# tusb3410.net
KiCad netlist of a schematic drawn in Altium Designer
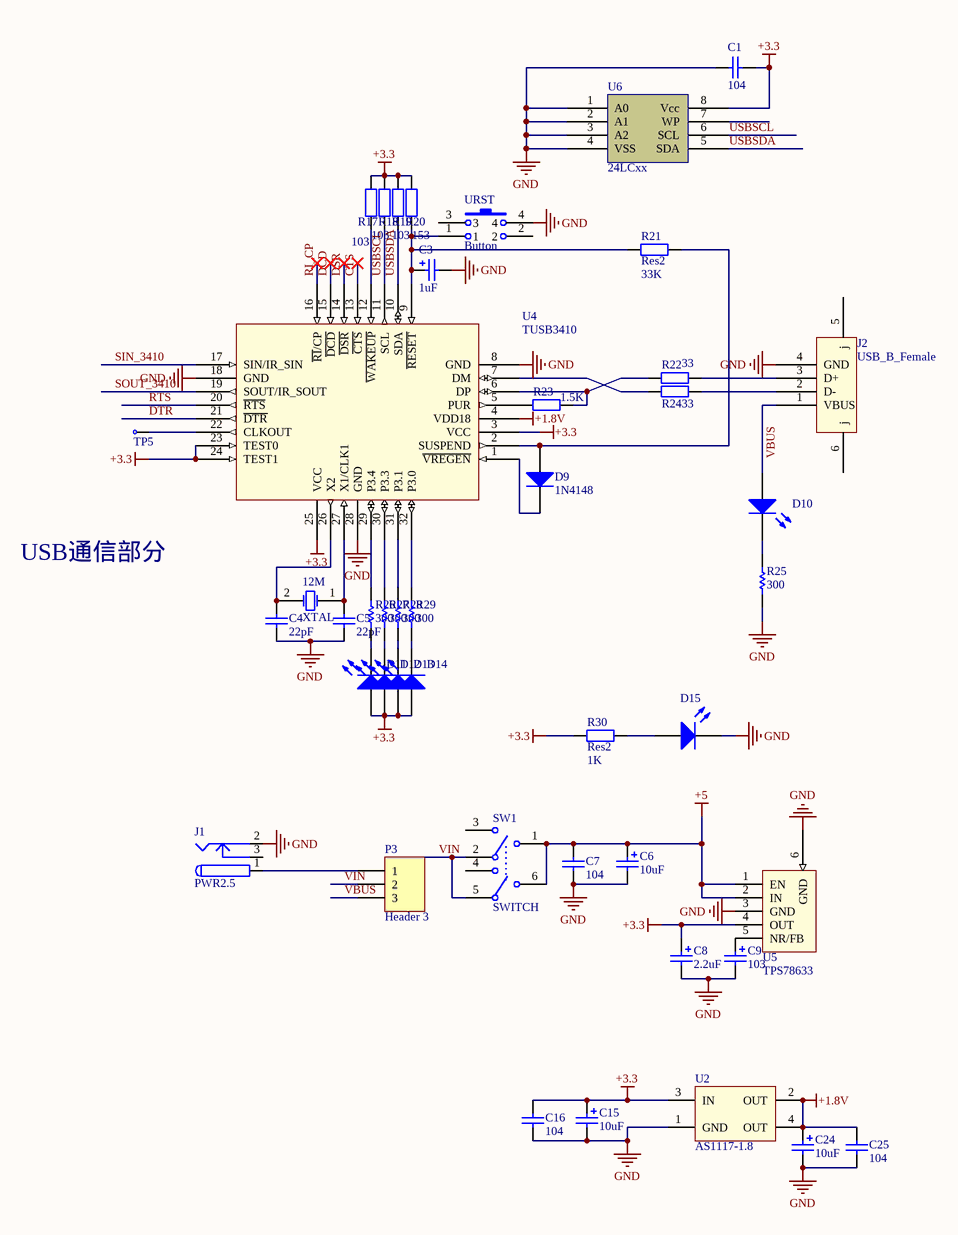
[diagram p0: tusb3410.SchDoc]

(export (version "E")
  (design (tool "Eeschema 10.0.6"))
  (components
    (comp (ref "12M")
      (value "XTAL")
      (footprint "GJA-M")
      (description "Crystal Oscillator")
      (fields (field (name "PUBLISHER") "Altium Limited"))
      (libsource (lib "WENSHI") (part "XTAL"))
    )
    (comp (ref "C1")
      (value "104")
      (footprint "C0805")
      (description "Capacitor")
      (fields (field (name "Comment") "Cap") (field (name "PUBLISHER") "Altium Limited"))
      (libsource (lib "WENSHI") (part "Cap"))
    )
    (comp (ref "C3")
      (value "1uF")
      (footprint "C5.3")
      (description "Polarized Capacitor (Radial)")
      (fields (field (name "Comment") "Cap Pol1") (field (name "PUBLISHER") "Altium Limited"))
      (libsource (lib "WENSHI") (part "Cap Pol1"))
    )
    (comp (ref "C4")
      (value "22pF")
      (footprint "C0805")
      (description "Capacitor")
      (fields (field (name "Comment") "Cap") (field (name "PUBLISHER") "Altium Limited"))
      (libsource (lib "Miscellaneous Devices") (part "Cap"))
    )
    (comp (ref "C5")
      (value "22pF")
      (footprint "C0805")
      (description "Capacitor")
      (fields (field (name "Comment") "Cap") (field (name "PUBLISHER") "Altium Limited"))
      (libsource (lib "Miscellaneous Devices") (part "Cap"))
    )
    (comp (ref "C6")
      (value "10uF")
      (footprint "C5.3")
      (description "Polarized Capacitor (Radial)")
      (fields (field (name "Comment") "Cap Pol1") (field (name "PUBLISHER") "Altium Limited"))
      (libsource (lib "WENSHI") (part "Cap Pol1"))
    )
    (comp (ref "C7")
      (value "104")
      (footprint "C0805")
      (description "Capacitor")
      (fields (field (name "Comment") "Cap") (field (name "PUBLISHER") "Altium Limited"))
      (libsource (lib "WENSHI") (part "Cap"))
    )
    (comp (ref "C8")
      (value "2.2uF")
      (footprint "C5.3")
      (description "Polarized Capacitor (Radial)")
      (fields (field (name "Comment") "Cap Pol1") (field (name "PUBLISHER") "Altium Limited"))
      (libsource (lib "WENSHI") (part "Cap Pol1"))
    )
    (comp (ref "C9")
      (value "103")
      (footprint "C5.3")
      (description "Polarized Capacitor (Radial)")
      (fields (field (name "Comment") "Cap Pol1") (field (name "PUBLISHER") "Altium Limited"))
      (libsource (lib "WENSHI") (part "Cap Pol1"))
    )
    (comp (ref "C15")
      (value "10uF")
      (footprint "C5.3")
      (description "Polarized Capacitor (Radial)")
      (fields (field (name "Comment") "Cap Pol1") (field (name "PUBLISHER") "Altium Limited"))
      (libsource (lib "WENSHI") (part "Cap Pol1"))
    )
    (comp (ref "C16")
      (value "104")
      (footprint "C0805")
      (description "Capacitor")
      (fields (field (name "Comment") "Cap") (field (name "PUBLISHER") "Altium Limited"))
      (libsource (lib "WENSHI") (part "Cap"))
    )
    (comp (ref "C24")
      (value "10uF")
      (footprint "C5.3")
      (description "Polarized Capacitor (Radial)")
      (fields (field (name "Comment") "Cap Pol1") (field (name "PUBLISHER") "Altium Limited"))
      (libsource (lib "WENSHI") (part "Cap Pol1"))
    )
    (comp (ref "C25")
      (value "104")
      (footprint "C0805")
      (description "Capacitor")
      (fields (field (name "Comment") "Cap") (field (name "PUBLISHER") "Altium Limited"))
      (libsource (lib "WENSHI") (part "Cap"))
    )
    (comp (ref "D9")
      (value "1N4148")
      (footprint "DO-35")
      (description "High Conductance Fast Diode")
      (fields (field (name "PUBLISHER") "Altium Limited"))
      (libsource (lib "Miscellaneous Devices") (part "Diode 1N4148"))
    )
    (comp (ref "D10")
      (value "LED1")
      (footprint "LED")
      (description "Typical RED GaAs LED")
      (fields (field (name "PUBLISHER") "Altium Limited"))
      (libsource (lib "WENSHI") (part "LED1"))
    )
    (comp (ref "D11")
      (value "LED1")
      (footprint "C0805")
      (description "Typical RED GaAs LED")
      (fields (field (name "PUBLISHER") "Altium Limited"))
      (libsource (lib "WENSHI") (part "LED1"))
    )
    (comp (ref "D12")
      (value "LED1")
      (footprint "C0805")
      (description "Typical RED GaAs LED")
      (fields (field (name "PUBLISHER") "Altium Limited"))
      (libsource (lib "WENSHI") (part "LED1"))
    )
    (comp (ref "D13")
      (value "LED1")
      (footprint "C0805")
      (description "Typical RED GaAs LED")
      (fields (field (name "PUBLISHER") "Altium Limited"))
      (libsource (lib "WENSHI") (part "LED1"))
    )
    (comp (ref "D14")
      (value "LED1")
      (footprint "C0805")
      (description "Typical RED GaAs LED")
      (fields (field (name "PUBLISHER") "Altium Limited"))
      (libsource (lib "WENSHI") (part "LED1"))
    )
    (comp (ref "D15")
      (value "LED1")
      (footprint "LED")
      (description "Typical RED GaAs LED")
      (fields (field (name "PUBLISHER") "Altium Limited"))
      (libsource (lib "WENSHI") (part "LED1"))
    )
    (comp (ref "J1")
      (value "PWR2.5")
      (footprint "DCJACK")
      (description "Low Voltage Power Supply Connector")
      (fields (field (name "PUBLISHER") "Altium Limited"))
      (libsource (lib "WENSHI") (part "PWR2.5"))
    )
    (comp (ref "J2")
      (value "USB_B_Female")
      (footprint "USB_B_Female")
      (libsource (lib "WENSHI") (part "USB_B_Female"))
    )
    (comp (ref "P3")
      (value "Header 3")
      (footprint "HDR1X3")
      (description "Header, 3-Pin")
      (fields (field (name "PUBLISHER") "Altium Limited"))
      (libsource (lib "Miscellaneous Connectors") (part "Header 3"))
    )
    (comp (ref "R17")
      (value "103")
      (footprint "c0805")
      (description "Resistor")
      (fields (field (name "Comment") "Res2") (field (name "PUBLISHER") "Altium Limited"))
      (libsource (lib "WENSHI") (part "Res2"))
    )
    (comp (ref "R18")
      (value "103")
      (footprint "c0805")
      (description "Resistor")
      (fields (field (name "Comment") "Res2") (field (name "PUBLISHER") "Altium Limited"))
      (libsource (lib "WENSHI") (part "Res2"))
    )
    (comp (ref "R19")
      (value "103")
      (footprint "c0805")
      (description "Resistor")
      (fields (field (name "Comment") "Res2") (field (name "PUBLISHER") "Altium Limited"))
      (libsource (lib "WENSHI") (part "Res2"))
    )
    (comp (ref "R20")
      (value "153")
      (footprint "c0805")
      (description "Resistor")
      (fields (field (name "Comment") "Res2") (field (name "PUBLISHER") "Altium Limited"))
      (libsource (lib "WENSHI") (part "Res2"))
    )
    (comp (ref "R21")
      (value "Res2")
      (footprint "c0805")
      (description "Resistor")
      (fields (field (name "ALTIUM_VALUE") "33K") (field (name "PUBLISHER") "Altium Limited"))
      (libsource (lib "") (part "Res2_1"))
    )
    (comp (ref "R22")
      (value "33")
      (footprint "c0805")
      (description "Resistor")
      (fields (field (name "Comment") "Res2") (field (name "PUBLISHER") "Altium Limited"))
      (libsource (lib "") (part "Res2_1"))
    )
    (comp (ref "R23")
      (value "1.5K")
      (footprint "c0805")
      (description "Resistor")
      (fields (field (name "Comment") "Res2") (field (name "PUBLISHER") "Altium Limited"))
      (libsource (lib "") (part "Res2_1"))
    )
    (comp (ref "R24")
      (value "33")
      (footprint "c0805")
      (description "Resistor")
      (fields (field (name "Comment") "Res2") (field (name "PUBLISHER") "Altium Limited"))
      (libsource (lib "") (part "Res2_1"))
    )
    (comp (ref "R25")
      (value "300")
      (footprint "C0805")
      (description "Resistor")
      (fields (field (name "Comment") "Res1") (field (name "PUBLISHER") "Altium Limited"))
      (libsource (lib "Miscellaneous Devices") (part "Res1"))
    )
    (comp (ref "R26")
      (value "300")
      (footprint "C0805")
      (description "Resistor")
      (fields (field (name "Comment") "Res1") (field (name "PUBLISHER") "Altium Limited"))
      (libsource (lib "Miscellaneous Devices") (part "Res1"))
    )
    (comp (ref "R27")
      (value "300")
      (footprint "C0805")
      (description "Resistor")
      (fields (field (name "Comment") "Res1") (field (name "PUBLISHER") "Altium Limited"))
      (libsource (lib "Miscellaneous Devices") (part "Res1"))
    )
    (comp (ref "R28")
      (value "300")
      (footprint "C0805")
      (description "Resistor")
      (fields (field (name "Comment") "Res1") (field (name "PUBLISHER") "Altium Limited"))
      (libsource (lib "Miscellaneous Devices") (part "Res1"))
    )
    (comp (ref "R29")
      (value "300")
      (footprint "C0805")
      (description "Resistor")
      (fields (field (name "Comment") "Res1") (field (name "PUBLISHER") "Altium Limited"))
      (libsource (lib "Miscellaneous Devices") (part "Res1"))
    )
    (comp (ref "R30")
      (value "Res2")
      (footprint "c0805")
      (description "Resistor")
      (fields (field (name "ALTIUM_VALUE") "1K") (field (name "PUBLISHER") "Altium Limited"))
      (libsource (lib "") (part "Res2_1"))
    )
    (comp (ref "SW1") (value "SWITCH") (footprint "DPDT-6") (libsource (lib "WENSHI") (part "SW-DPDT")))
    (comp (ref "TP5")
      (value "TestPoint")
      (footprint "TESTPOINT")
      (description "TespPoint")
      (libsource (lib "2812") (part "TestPoint"))
    )
    (comp (ref "U2")
      (value "AS1117-1.8")
      (footprint "SOT-223")
      (libsource (lib "WENSHI") (part "AS1117-3.3"))
    )
    (comp (ref "U4")
      (value "TUSB3410")
      (footprint "DMC68HC908JL8")
      (libsource (lib "TUSB3410") (part "TUSB3410"))
    )
    (comp (ref "U5")
      (value "TPS78633")
      (footprint "PSFM_G5")
      (description "3.3V Power")
      (libsource (lib "WENSHI") (part "TPS78633"))
    )
    (comp (ref "U6") (value "24LCxx") (footprint "DIP-8") (libsource (lib "2812") (part "24LCxx")))
    (comp (ref "URST") (value "Button") (footprint "SW-6") (libsource (lib "WENSHI") (part "Button_4")))
  )
  (nets
    (net (code "1") (name "+1.8V") (class "Default")
      (node (ref "C24") (pin "1") (pinfunction "1_1") (pintype "passive"))
      (node (ref "C25") (pin "2") (pinfunction "2_2") (pintype "passive"))
      (node (ref "U2") (pin "2") (pinfunction "OUT_2") (pintype "passive"))
      (node (ref "U2") (pin "4") (pinfunction "OUT_4") (pintype "passive"))
      (node (ref "U4") (pin "4") (pinfunction "VDD18_4") (pintype "power_in"))
    )
    (net (code "2") (name "+3.3") (class "Default")
      (node (ref "C1") (pin "2") (pinfunction "2_2") (pintype "passive"))
      (node (ref "C15") (pin "1") (pinfunction "1_1") (pintype "passive"))
      (node (ref "C16") (pin "2") (pinfunction "2_2") (pintype "passive"))
      (node (ref "C8") (pin "1") (pinfunction "1_1") (pintype "passive"))
      (node (ref "D11") (pin "1") (pinfunction "A_1") (pintype "passive"))
      (node (ref "D12") (pin "1") (pinfunction "A_1") (pintype "passive"))
      (node (ref "D13") (pin "1") (pinfunction "A_1") (pintype "passive"))
      (node (ref "D14") (pin "1") (pinfunction "A_1") (pintype "passive"))
      (node (ref "R17") (pin "2") (pinfunction "2_2") (pintype "passive"))
      (node (ref "R18") (pin "2") (pinfunction "2_2") (pintype "passive"))
      (node (ref "R19") (pin "2") (pinfunction "2_2") (pintype "passive"))
      (node (ref "R20") (pin "2") (pinfunction "2_2") (pintype "passive"))
      (node (ref "R30") (pin "1") (pinfunction "1_1") (pintype "passive"))
      (node (ref "U2") (pin "3") (pinfunction "IN_3") (pintype "passive"))
      (node (ref "U4") (pin "23") (pinfunction "TEST0_23") (pintype "input"))
      (node (ref "U4") (pin "24") (pinfunction "TEST1_24") (pintype "input"))
      (node (ref "U4") (pin "25") (pinfunction "VCC_25") (pintype "power_in"))
      (node (ref "U4") (pin "3") (pinfunction "VCC_3") (pintype "power_in"))
      (node (ref "U5") (pin "4") (pinfunction "OUT_4") (pintype "passive"))
      (node (ref "U6") (pin "8") (pinfunction "Vcc_8") (pintype "passive"))
    )
    (net (code "3") (name "+5") (class "Default")
      (node (ref "C6") (pin "1") (pinfunction "1_1") (pintype "passive"))
      (node (ref "C7") (pin "2") (pinfunction "2_2") (pintype "passive"))
      (node (ref "SW1") (pin "1") (pinfunction "1_1") (pintype "passive"))
      (node (ref "SW1") (pin "6") (pinfunction "6_6") (pintype "passive"))
      (node (ref "U5") (pin "1") (pinfunction "EN_1") (pintype "passive"))
      (node (ref "U5") (pin "2") (pinfunction "IN_2") (pintype "passive"))
    )
    (net (code "4") (name "/CTS") (class "Default")
      (node (ref "U4") (pin "13") (pinfunction "~{CTS}_13") (pintype "input+no_connect"))
    )
    (net (code "5") (name "/DCD") (class "Default")
      (node (ref "U4") (pin "15") (pinfunction "~{DCD}_15") (pintype "input+no_connect"))
    )
    (net (code "6") (name "/DSR") (class "Default")
      (node (ref "U4") (pin "14") (pinfunction "~{DSR}_14") (pintype "input+no_connect"))
    )
    (net (code "7") (name "/DTR") (class "Default")
      (node (ref "U4") (pin "21") (pinfunction "~{DTR}_21") (pintype "output"))
    )
    (net (code "8") (name "/RI_CP") (class "Default")
      (node (ref "U4") (pin "16") (pinfunction "~{RI}/CP_16") (pintype "input+no_connect"))
    )
    (net (code "9") (name "/RTS") (class "Default")
      (node (ref "U4") (pin "20") (pinfunction "~{RTS}_20") (pintype "output"))
    )
    (net (code "10") (name "/SIN_3410") (class "Default")
      (node (ref "U4") (pin "17") (pinfunction "SIN/IR_SIN_17") (pintype "input"))
    )
    (net (code "11") (name "/SOUT_3410") (class "Default")
      (node (ref "U4") (pin "19") (pinfunction "SOUT/IR_SOUT_19") (pintype "output"))
    )
    (net (code "12") (name "/USBSCL") (class "Default")
      (node (ref "R18") (pin "1") (pinfunction "1_1") (pintype "passive"))
      (node (ref "U4") (pin "11") (pinfunction "SCL_11") (pintype "output"))
      (node (ref "U6") (pin "6") (pinfunction "SCL_6") (pintype "passive"))
    )
    (net (code "13") (name "/USBSDA") (class "Default")
      (node (ref "R19") (pin "1") (pinfunction "1_1") (pintype "passive"))
      (node (ref "U4") (pin "10") (pinfunction "SDA_10") (pintype "bidirectional"))
      (node (ref "U6") (pin "5") (pinfunction "SDA_5") (pintype "passive"))
    )
    (net (code "14") (name "/VBUS") (class "Default")
      (node (ref "D10") (pin "1") (pinfunction "A_1") (pintype "passive"))
      (node (ref "J2") (pin "1") (pinfunction "VBUS_1") (pintype "power_in"))
      (node (ref "P3") (pin "3") (pinfunction "3_3") (pintype "passive"))
    )
    (net (code "15") (name "/VIN") (class "Default")
      (node (ref "P3") (pin "2") (pinfunction "2_2") (pintype "passive"))
      (node (ref "SW1") (pin "2") (pinfunction "2_2") (pintype "passive"))
      (node (ref "SW1") (pin "5") (pinfunction "5_5") (pintype "passive"))
    )
    (net (code "16") (name "GND") (class "Default")
      (node (ref "C1") (pin "1") (pinfunction "1_1") (pintype "passive"))
      (node (ref "C15") (pin "2") (pinfunction "2_2") (pintype "passive"))
      (node (ref "C16") (pin "1") (pinfunction "1_1") (pintype "passive"))
      (node (ref "C24") (pin "2") (pinfunction "2_2") (pintype "passive"))
      (node (ref "C25") (pin "1") (pinfunction "1_1") (pintype "passive"))
      (node (ref "C3") (pin "2") (pinfunction "2_2") (pintype "passive"))
      (node (ref "C4") (pin "2") (pinfunction "2_2") (pintype "passive"))
      (node (ref "C5") (pin "2") (pinfunction "2_2") (pintype "passive"))
      (node (ref "C6") (pin "2") (pinfunction "2_2") (pintype "passive"))
      (node (ref "C7") (pin "1") (pinfunction "1_1") (pintype "passive"))
      (node (ref "C8") (pin "2") (pinfunction "2_2") (pintype "passive"))
      (node (ref "C9") (pin "2") (pinfunction "2_2") (pintype "passive"))
      (node (ref "D15") (pin "2") (pinfunction "K_2") (pintype "passive"))
      (node (ref "J1") (pin "2") (pinfunction "2_2") (pintype "power_in"))
      (node (ref "J2") (pin "4") (pinfunction "GND_4") (pintype "power_in"))
      (node (ref "R25") (pin "1") (pinfunction "1_1") (pintype "passive"))
      (node (ref "U2") (pin "1") (pinfunction "GND_1") (pintype "passive"))
      (node (ref "U4") (pin "18") (pinfunction "GND_18") (pintype "power_in"))
      (node (ref "U4") (pin "28") (pinfunction "GND_28") (pintype "power_in"))
      (node (ref "U4") (pin "8") (pinfunction "GND_8") (pintype "power_in"))
      (node (ref "U5") (pin "3") (pinfunction "GND_3") (pintype "passive"))
      (node (ref "U5") (pin "6") (pinfunction "GND_6") (pintype "input"))
      (node (ref "U6") (pin "1") (pinfunction "A0_1") (pintype "passive"))
      (node (ref "U6") (pin "2") (pinfunction "A1_2") (pintype "passive"))
      (node (ref "U6") (pin "3") (pinfunction "A2_3") (pintype "passive"))
      (node (ref "U6") (pin "4") (pinfunction "VSS_4") (pintype "passive"))
      (node (ref "URST") (pin "4") (pinfunction "4_4") (pintype "passive"))
    )
    (net (code "17") (name "Net-(12M-OSC1)") (class "Default")
      (node (ref "12M") (pin "1") (pinfunction "OSC1_1") (pintype "passive"))
      (node (ref "C5") (pin "1") (pinfunction "1_1") (pintype "passive"))
      (node (ref "U4") (pin "27") (pinfunction "X1/CLK1_27") (pintype "input"))
    )
    (net (code "18") (name "Net-(12M-OSC2)") (class "Default")
      (node (ref "12M") (pin "2") (pinfunction "OSC2_2") (pintype "passive"))
      (node (ref "C4") (pin "1") (pinfunction "1_1") (pintype "passive"))
      (node (ref "U4") (pin "26") (pinfunction "X2_26") (pintype "output"))
    )
    (net (code "19") (name "Net-(D9-A)") (class "Default")
      (node (ref "D9") (pin "1") (pinfunction "A_1") (pintype "passive"))
      (node (ref "R21") (pin "2") (pinfunction "2_2") (pintype "passive"))
      (node (ref "U4") (pin "2") (pinfunction "SUSPEND_2") (pintype "output"))
    )
    (net (code "20") (name "Net-(D9-K)") (class "Default")
      (node (ref "D9") (pin "2") (pinfunction "K_2") (pintype "passive"))
      (node (ref "U4") (pin "1") (pinfunction "~{VREGEN}_1") (pintype "input"))
    )
    (net (code "21") (name "Net-(D10-K)") (class "Default")
      (node (ref "D10") (pin "2") (pinfunction "K_2") (pintype "passive"))
      (node (ref "R25") (pin "2") (pinfunction "2_2") (pintype "passive"))
    )
    (net (code "22") (name "Net-(D11-K)") (class "Default")
      (node (ref "D11") (pin "2") (pinfunction "K_2") (pintype "passive"))
      (node (ref "R26") (pin "2") (pinfunction "2_2") (pintype "passive"))
    )
    (net (code "23") (name "Net-(D12-K)") (class "Default")
      (node (ref "D12") (pin "2") (pinfunction "K_2") (pintype "passive"))
      (node (ref "R27") (pin "2") (pinfunction "2_2") (pintype "passive"))
    )
    (net (code "24") (name "Net-(D13-K)") (class "Default")
      (node (ref "D13") (pin "2") (pinfunction "K_2") (pintype "passive"))
      (node (ref "R28") (pin "2") (pinfunction "2_2") (pintype "passive"))
    )
    (net (code "25") (name "Net-(D14-K)") (class "Default")
      (node (ref "D14") (pin "2") (pinfunction "K_2") (pintype "passive"))
      (node (ref "R29") (pin "2") (pinfunction "2_2") (pintype "passive"))
    )
    (net (code "26") (name "Net-(D15-A)") (class "Default")
      (node (ref "D15") (pin "1") (pinfunction "A_1") (pintype "passive"))
      (node (ref "R30") (pin "2") (pinfunction "2_2") (pintype "passive"))
    )
    (net (code "27") (name "Net-(J1-Pad1)") (class "Default")
      (node (ref "J1") (pin "1") (pinfunction "1_1") (pintype "power_in"))
      (node (ref "P3") (pin "1") (pinfunction "1_1") (pintype "passive"))
    )
    (net (code "28") (name "Net-(J2-D+)") (class "Default")
      (node (ref "J2") (pin "3") (pinfunction "D+_3") (pintype "power_in"))
      (node (ref "R22") (pin "2") (pinfunction "2_2") (pintype "passive"))
    )
    (net (code "29") (name "Net-(J2-D-)") (class "Default")
      (node (ref "J2") (pin "2") (pinfunction "D-_2") (pintype "power_in"))
      (node (ref "R24") (pin "2") (pinfunction "2_2") (pintype "passive"))
    )
    (net (code "30") (name "Net-(TP5-TP)") (class "Default")
      (node (ref "TP5") (pin "1") (pinfunction "TP_1") (pintype "passive"))
      (node (ref "U4") (pin "22") (pinfunction "CLKOUT_22") (pintype "output"))
    )
    (net (code "31") (name "Net-(U4-DM)") (class "Default")
      (node (ref "R24") (pin "1") (pinfunction "1_1") (pintype "passive"))
      (node (ref "U4") (pin "7") (pinfunction "DM_7") (pintype "bidirectional"))
    )
    (net (code "32") (name "Net-(U4-DP)") (class "Default")
      (node (ref "R22") (pin "1") (pinfunction "1_1") (pintype "passive"))
      (node (ref "R23") (pin "2") (pinfunction "2_2") (pintype "passive"))
      (node (ref "U4") (pin "6") (pinfunction "DP_6") (pintype "bidirectional"))
    )
    (net (code "33") (name "Net-(U4-P3.0)") (class "Default")
      (node (ref "R29") (pin "1") (pinfunction "1_1") (pintype "passive"))
      (node (ref "U4") (pin "32") (pinfunction "P3.0_32") (pintype "bidirectional"))
    )
    (net (code "34") (name "Net-(U4-P3.1)") (class "Default")
      (node (ref "R28") (pin "1") (pinfunction "1_1") (pintype "passive"))
      (node (ref "U4") (pin "31") (pinfunction "P3.1_31") (pintype "bidirectional"))
    )
    (net (code "35") (name "Net-(U4-P3.3)") (class "Default")
      (node (ref "R27") (pin "1") (pinfunction "1_1") (pintype "passive"))
      (node (ref "U4") (pin "30") (pinfunction "P3.3_30") (pintype "bidirectional"))
    )
    (net (code "36") (name "Net-(U4-P3.4)") (class "Default")
      (node (ref "R26") (pin "1") (pinfunction "1_1") (pintype "passive"))
      (node (ref "U4") (pin "29") (pinfunction "P3.4_29") (pintype "bidirectional"))
    )
    (net (code "37") (name "Net-(U4-PUR)") (class "Default")
      (node (ref "R23") (pin "1") (pinfunction "1_1") (pintype "passive"))
      (node (ref "U4") (pin "5") (pinfunction "PUR_5") (pintype "output"))
    )
    (net (code "38") (name "Net-(U4-~{RESET})") (class "Default")
      (node (ref "C3") (pin "1") (pinfunction "1_1") (pintype "passive"))
      (node (ref "R20") (pin "1") (pinfunction "1_1") (pintype "passive"))
      (node (ref "R21") (pin "1") (pinfunction "1_1") (pintype "passive"))
      (node (ref "U4") (pin "9") (pinfunction "~{RESET}_9") (pintype "input"))
      (node (ref "URST") (pin "1") (pinfunction "1_1") (pintype "passive"))
    )
    (net (code "39") (name "Net-(U4-~{WAKEUP})") (class "Default")
      (node (ref "R17") (pin "1") (pinfunction "1_1") (pintype "passive"))
      (node (ref "U4") (pin "12") (pinfunction "~{WAKEUP}_12") (pintype "input"))
    )
    (net (code "40") (name "Net-(U5-NR{slash}FB)") (class "Default")
      (node (ref "C9") (pin "1") (pinfunction "1_1") (pintype "passive"))
      (node (ref "U5") (pin "5") (pinfunction "NR/FB_5") (pintype "passive"))
    )
    (net (code "41") (name "unconnected-(J1-Pad3)") (class "Default")
      (node (ref "J1") (pin "3") (pinfunction "3_3") (pintype "power_in"))
    )
    (net (code "42") (name "unconnected-(J2-j-Pad5)") (class "Default")
      (node (ref "J2") (pin "5") (pinfunction "j_5") (pintype "power_in"))
    )
    (net (code "43") (name "unconnected-(J2-j-Pad6)") (class "Default")
      (node (ref "J2") (pin "6") (pinfunction "j_6") (pintype "power_in"))
    )
    (net (code "44") (name "unconnected-(SW1-Pad3)") (class "Default")
      (node (ref "SW1") (pin "3") (pinfunction "3_3") (pintype "passive"))
    )
    (net (code "45") (name "unconnected-(SW1-Pad4)") (class "Default")
      (node (ref "SW1") (pin "4") (pinfunction "4_4") (pintype "passive"))
    )
    (net (code "46") (name "unconnected-(U6-WP-Pad7)") (class "Default")
      (node (ref "U6") (pin "7") (pinfunction "WP_7") (pintype "passive"))
    )
    (net (code "47") (name "unconnected-(URST-Pad2)") (class "Default")
      (node (ref "URST") (pin "2") (pinfunction "2_2") (pintype "passive"))
    )
    (net (code "48") (name "unconnected-(URST-Pad3)") (class "Default")
      (node (ref "URST") (pin "3") (pinfunction "3_3") (pintype "passive"))
    )
  )
)
